# Squama_Ethernet.net
KiCad netlist of a schematic drawn in EAGLE
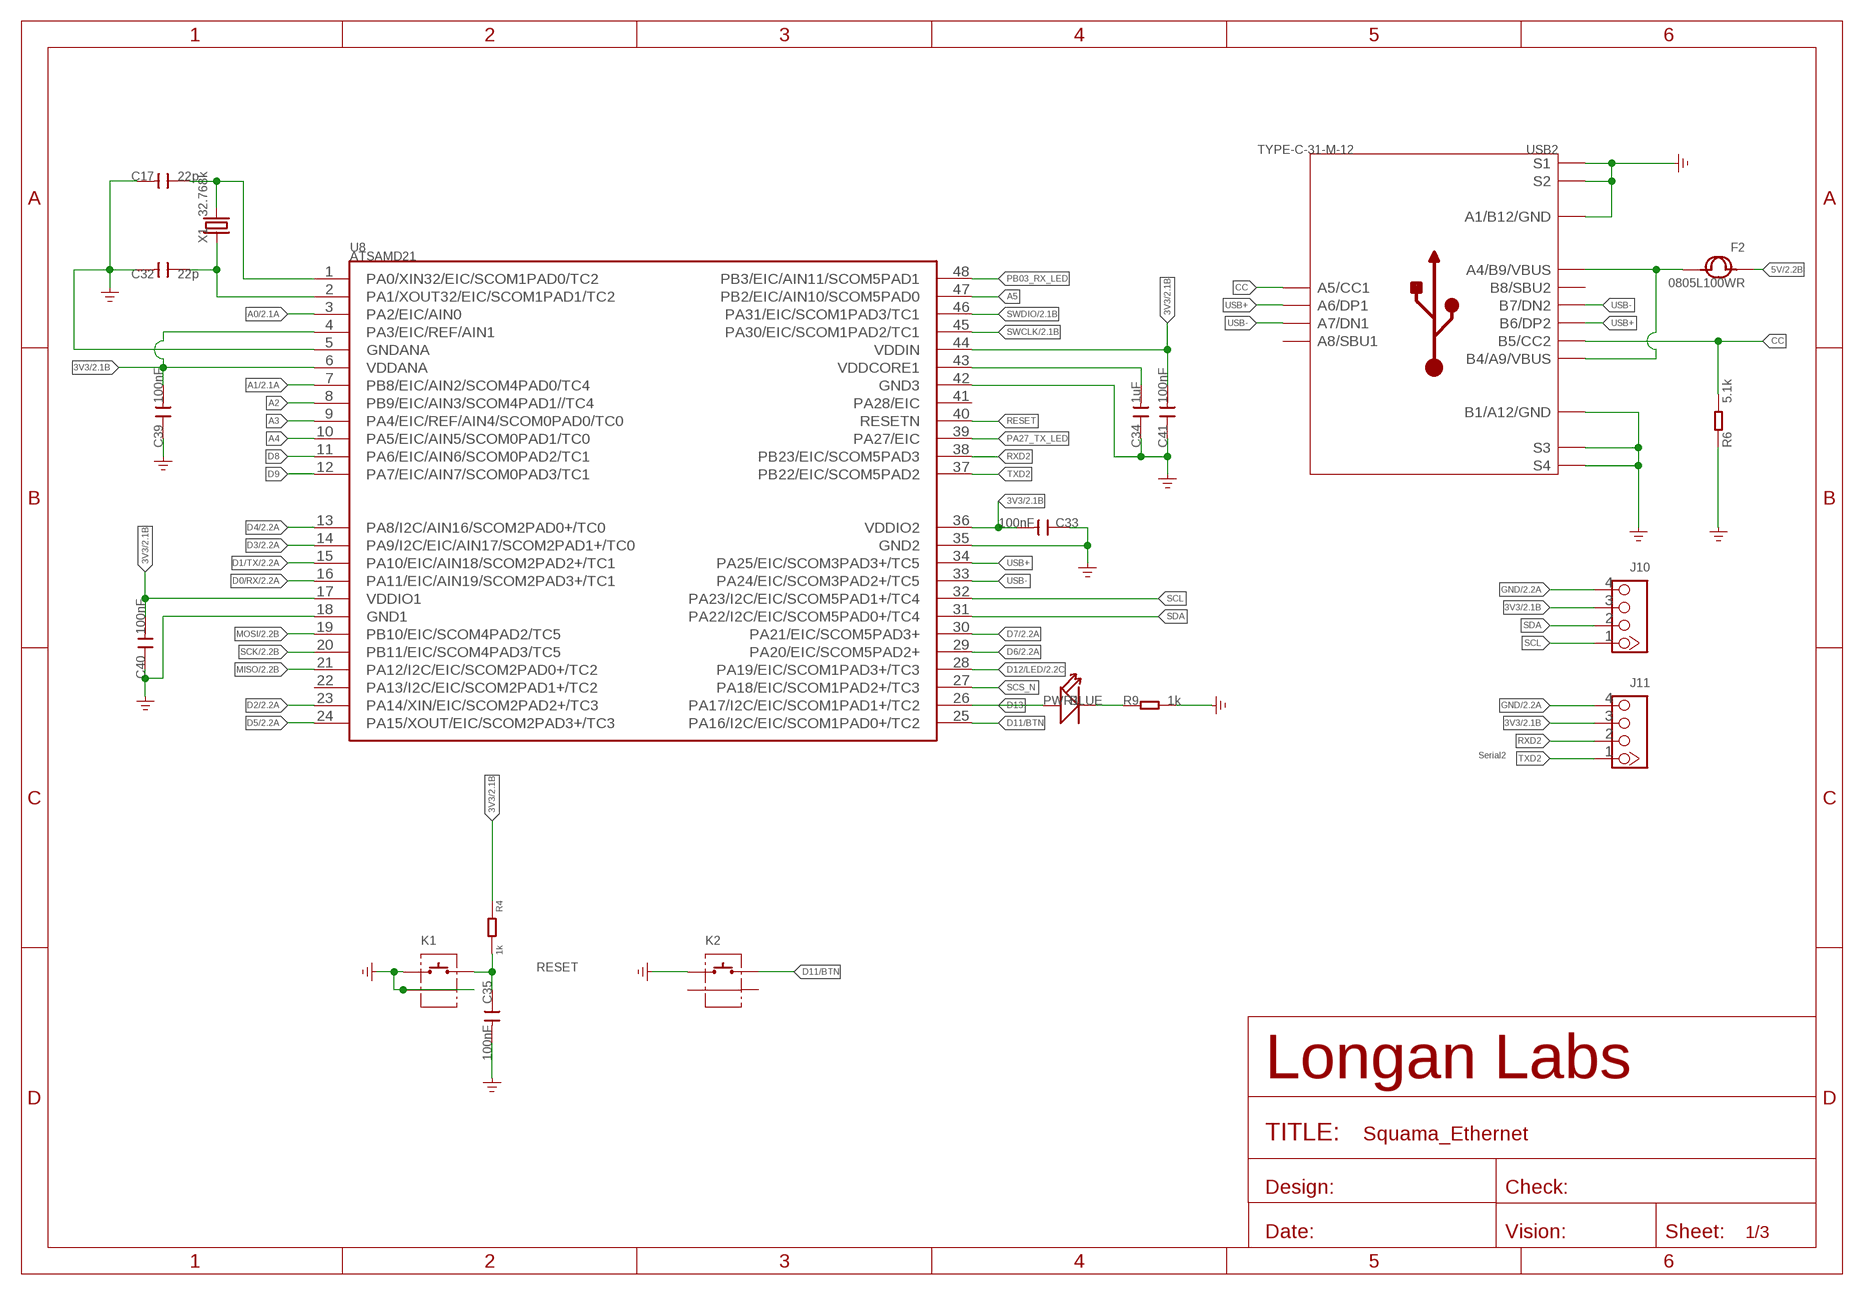
[diagram p0: schematic, sheet 1]
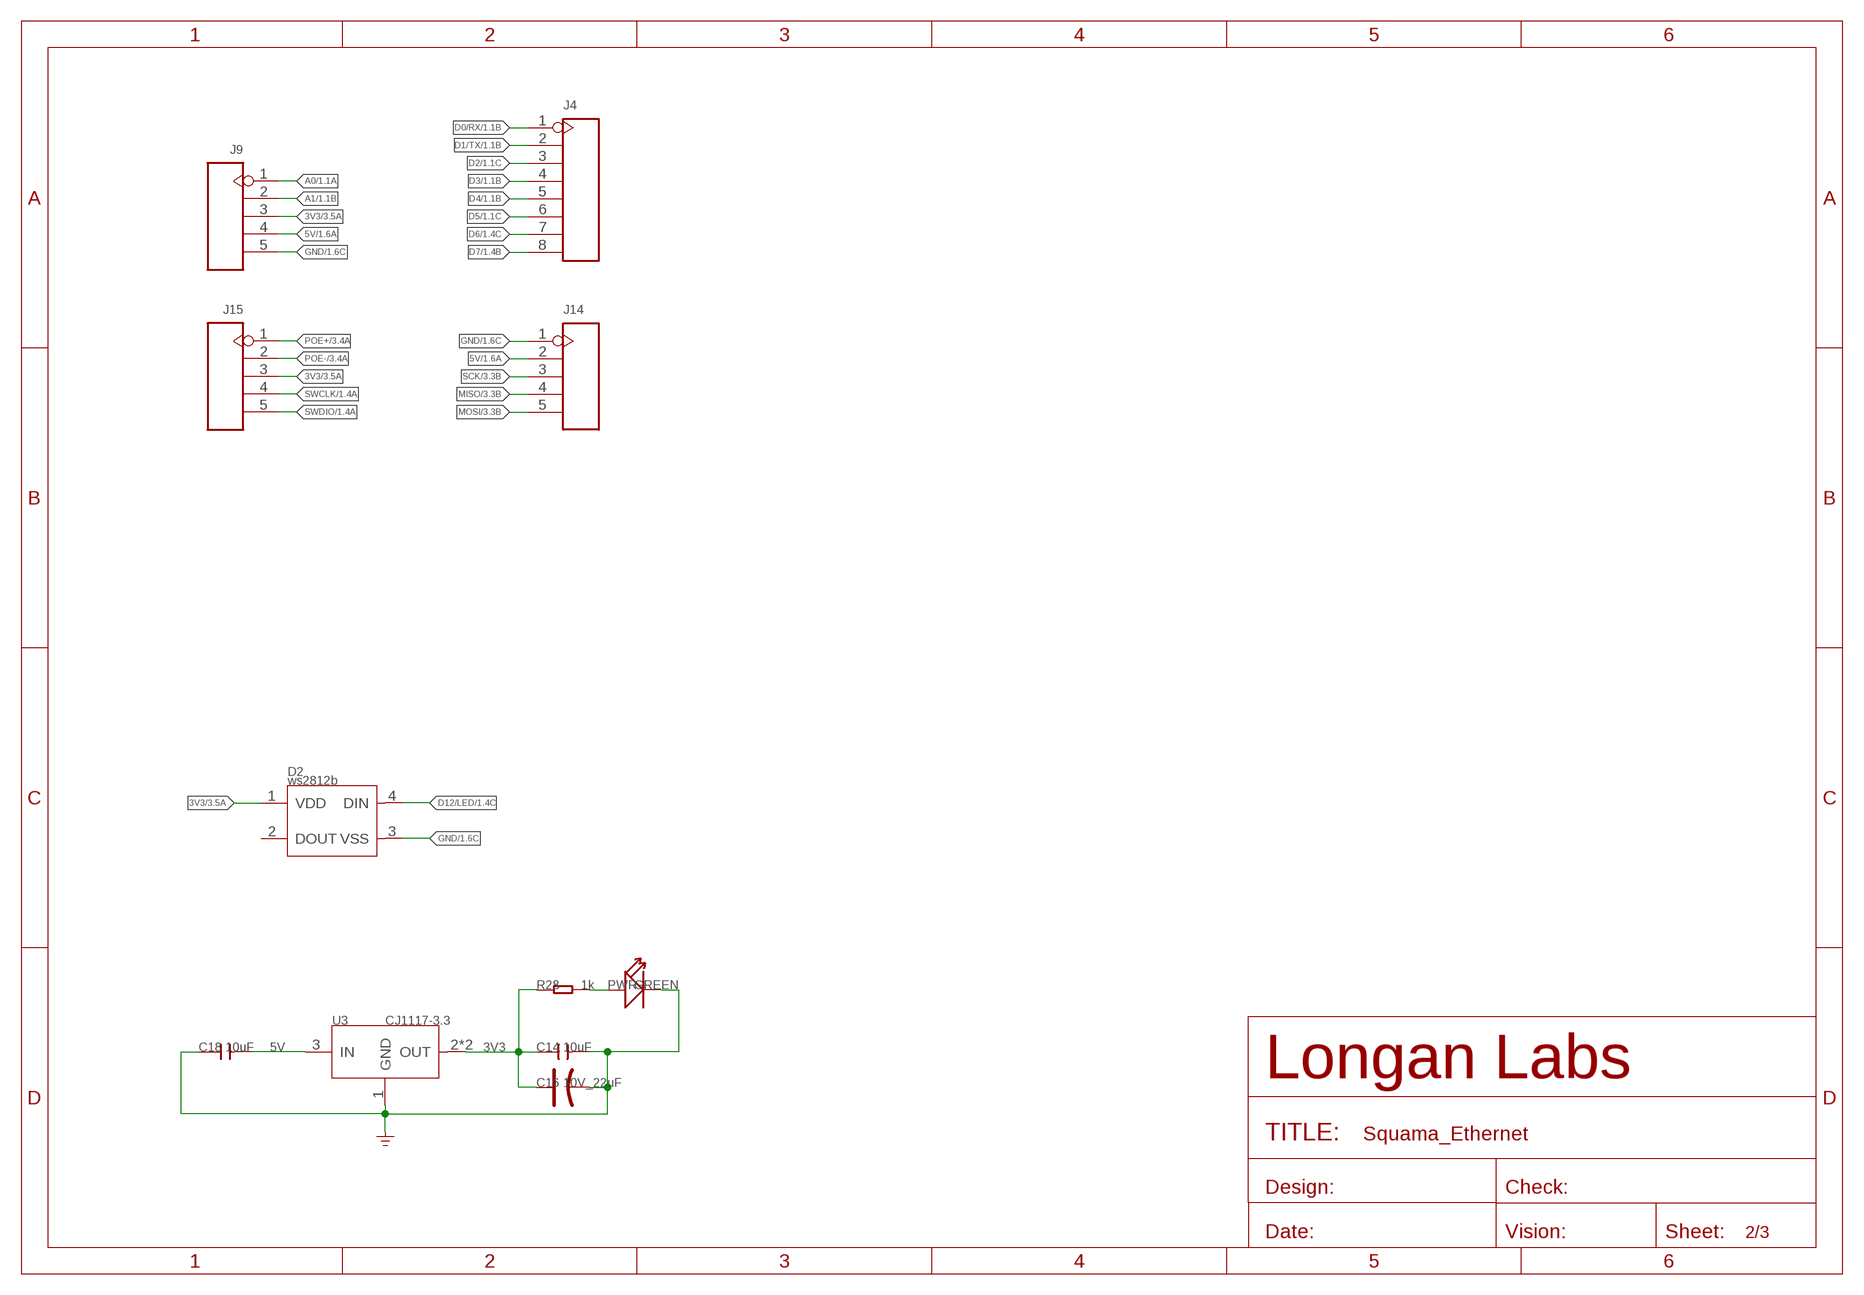
[diagram p1: schematic, sheet 2]
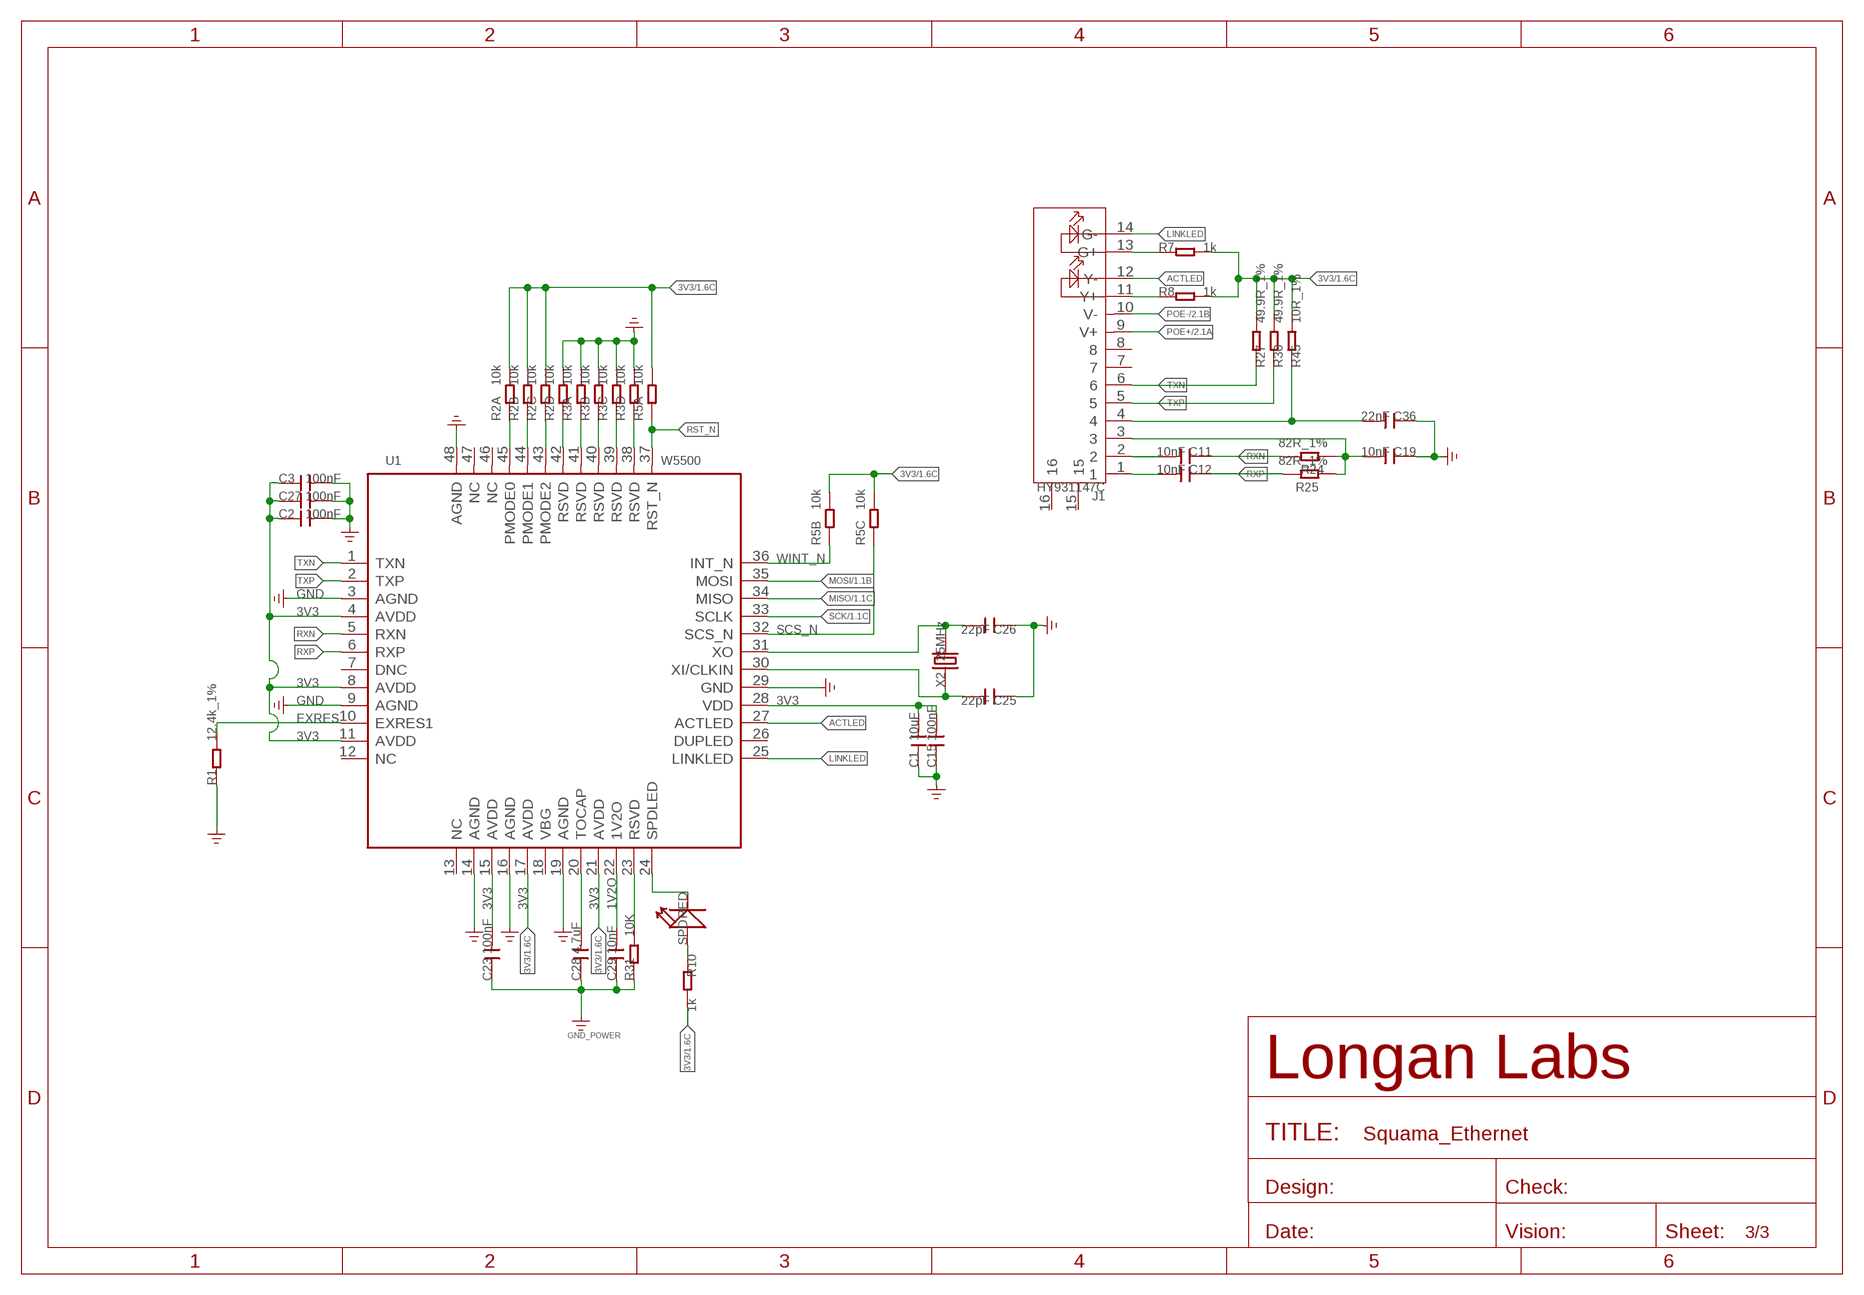
[diagram p2: schematic, sheet 3]

(export (version "E")
  (design (tool "Eeschema 10.0.6"))
  (components
    (comp (ref "C1")
      (value "10uF")
      (footprint "eagle-import:C0603")
      (libsource (lib "eagle-import") (part "C-0603"))
    )
    (comp (ref "C2")
      (value "100nF")
      (footprint "eagle-import:C0603")
      (libsource (lib "eagle-import") (part "C-0603"))
    )
    (comp (ref "C3")
      (value "100nF")
      (footprint "eagle-import:C0603")
      (libsource (lib "eagle-import") (part "C-0603"))
    )
    (comp (ref "C11")
      (value "10nF")
      (footprint "eagle-import:C0603")
      (libsource (lib "eagle-import") (part "C-0603"))
    )
    (comp (ref "C12")
      (value "10nF")
      (footprint "eagle-import:C0603")
      (libsource (lib "eagle-import") (part "C-0603"))
    )
    (comp (ref "C15")
      (value "100nF")
      (footprint "eagle-import:C0603")
      (libsource (lib "eagle-import") (part "C-0603"))
    )
    (comp (ref "C19")
      (value "10nF")
      (footprint "eagle-import:C0603")
      (libsource (lib "eagle-import") (part "C-0603"))
    )
    (comp (ref "C23")
      (value "100nF")
      (footprint "eagle-import:C0603")
      (libsource (lib "eagle-import") (part "C-0603"))
    )
    (comp (ref "C25")
      (value "22pF")
      (footprint "eagle-import:C0603")
      (libsource (lib "eagle-import") (part "C-0603"))
    )
    (comp (ref "C26")
      (value "22pF")
      (footprint "eagle-import:C0603")
      (libsource (lib "eagle-import") (part "C-0603"))
    )
    (comp (ref "C27")
      (value "100nF")
      (footprint "eagle-import:C0603")
      (libsource (lib "eagle-import") (part "C-0603"))
    )
    (comp (ref "C28")
      (value "4.7uF")
      (footprint "eagle-import:C0805")
      (libsource (lib "eagle-import") (part "C-0805"))
    )
    (comp (ref "C29")
      (value "10nF")
      (footprint "eagle-import:C0603")
      (libsource (lib "eagle-import") (part "C-0603"))
    )
    (comp (ref "C36")
      (value "22nF")
      (footprint "eagle-import:C0603")
      (libsource (lib "eagle-import") (part "C-0603"))
    )
    (comp (ref "J1")
      (value "HY931147C")
      (footprint "eagle-import:RJ45-14+2P-16.1X21.6X13.95MM")
      (libsource (lib "eagle-import") (part "RJ45-HY931147C"))
    )
    (comp (ref "R1")
      (value "12.4k_1%")
      (footprint "eagle-import:R0603")
      (libsource (lib "eagle-import") (part "R-0603"))
    )
    (comp (ref "R2")
      (value "10k")
      (footprint "eagle-import:R0804-8")
      (libsource (lib "eagle-import") (part "RES-ARRAY-0804"))
    )
    (comp (ref "R3")
      (value "10k")
      (footprint "eagle-import:R0804-8")
      (libsource (lib "eagle-import") (part "RES-ARRAY-0804"))
    )
    (comp (ref "R5")
      (value "10k")
      (footprint "eagle-import:R0804-8")
      (libsource (lib "eagle-import") (part "RES-ARRAY-0804"))
    )
    (comp (ref "R7")
      (value "1k")
      (footprint "eagle-import:R0603")
      (libsource (lib "eagle-import") (part "R-0603"))
    )
    (comp (ref "R8")
      (value "1k")
      (footprint "eagle-import:R0603")
      (libsource (lib "eagle-import") (part "R-0603"))
    )
    (comp (ref "R10")
      (value "1k")
      (footprint "eagle-import:R0603")
      (libsource (lib "eagle-import") (part "R-0603"))
    )
    (comp (ref "R24")
      (value "82R_1%")
      (footprint "eagle-import:R0603")
      (libsource (lib "eagle-import") (part "R-0603"))
    )
    (comp (ref "R25")
      (value "82R_1%")
      (footprint "eagle-import:R0603")
      (libsource (lib "eagle-import") (part "R-0603"))
    )
    (comp (ref "R27")
      (value "49.9R_1%")
      (footprint "eagle-import:R0603")
      (libsource (lib "eagle-import") (part "R-0603"))
    )
    (comp (ref "R30")
      (value "49.9R_1%")
      (footprint "eagle-import:R0603")
      (libsource (lib "eagle-import") (part "R-0603"))
    )
    (comp (ref "R31")
      (value "10K")
      (footprint "eagle-import:R0603")
      (libsource (lib "eagle-import") (part "R-0603"))
    )
    (comp (ref "R45")
      (value "10R_1%")
      (footprint "eagle-import:R0603")
      (libsource (lib "eagle-import") (part "R-0603"))
    )
    (comp (ref "SPD")
      (value "RED")
      (footprint "eagle-import:LED-0603")
      (libsource (lib "eagle-import") (part "LED'0603'"))
    )
    (comp (ref "U1")
      (value "W5500")
      (footprint "eagle-import:LQFP-48")
      (libsource (lib "eagle-import") (part "DRIVER-W5500"))
    )
    (comp (ref "X2")
      (value "25MHz")
      (footprint "eagle-import:2P-SMD-5X3.2")
      (libsource (lib "eagle-import") (part "CRYSTAL'5032'"))
    )
    (comp (ref "C14")
      (value "10uF")
      (footprint "eagle-import:C0805")
      (libsource (lib "eagle-import") (part "C-0805"))
    )
    (comp (ref "C16")
      (value "10V_22uF")
      (footprint "eagle-import:AVX-B")
      (libsource (lib "eagle-import") (part "CAP-AVX-B"))
    )
    (comp (ref "C18")
      (value "10uF")
      (footprint "eagle-import:C0805")
      (libsource (lib "eagle-import") (part "C-0805"))
    )
    (comp (ref "D2")
      (value "ws2812b")
      (footprint "eagle-import:LED4-SMD-5050")
      (libsource (lib "eagle-import") (part "LED-RGB-4P-WS2812B-304990003"))
    )
    (comp (ref "J4")
      (value "HEADER-8P-80/40MIL")
      (footprint "eagle-import:H8-2.54-C80D40MIL")
      (libsource (lib "eagle-import") (part "HEADER-8P-80/40MIL"))
    )
    (comp (ref "J9")
      (value "HEADER-5P-2.54")
      (footprint "eagle-import:H5-2.54")
      (libsource (lib "eagle-import") (part "HEADER-5P-2.54"))
    )
    (comp (ref "J14")
      (value "HEADER-5P-2.0")
      (footprint "eagle-import:H5-2.0")
      (libsource (lib "eagle-import") (part "HEADER-5P-2.0"))
    )
    (comp (ref "J15")
      (value "HEADER-5P-2.0")
      (footprint "eagle-import:H5-2.0")
      (libsource (lib "eagle-import") (part "HEADER-5P-2.0"))
    )
    (comp (ref "PWR")
      (value "GREEN")
      (footprint "eagle-import:LED-0603")
      (libsource (lib "eagle-import") (part "LED'0603'"))
    )
    (comp (ref "R28")
      (value "1k")
      (footprint "eagle-import:R0603")
      (libsource (lib "eagle-import") (part "R-0603"))
    )
    (comp (ref "U3")
      (value "CJ1117-3.3")
      (footprint "eagle-import:SOT-89")
      (libsource (lib "eagle-import") (part "PMIC-CJ1117'SOT89'"))
    )
    (comp (ref "C17")
      (value "22p")
      (footprint "eagle-import:C0603")
      (libsource (lib "eagle-import") (part "CAP-0603"))
    )
    (comp (ref "C32")
      (value "22p")
      (footprint "eagle-import:C0603")
      (libsource (lib "eagle-import") (part "CAP-0603"))
    )
    (comp (ref "C33")
      (value "100nF")
      (footprint "eagle-import:C0603")
      (libsource (lib "eagle-import") (part "CAP-0603"))
    )
    (comp (ref "C34")
      (value "1uF")
      (footprint "eagle-import:C0603")
      (libsource (lib "eagle-import") (part "CAP-0603"))
    )
    (comp (ref "C35")
      (value "100nF")
      (footprint "eagle-import:C0603")
      (libsource (lib "eagle-import") (part "CAP-0603"))
    )
    (comp (ref "C39")
      (value "100nF")
      (footprint "eagle-import:C0603")
      (libsource (lib "eagle-import") (part "CAP-0603"))
    )
    (comp (ref "C40")
      (value "100nF")
      (footprint "eagle-import:C0603")
      (libsource (lib "eagle-import") (part "CAP-0603"))
    )
    (comp (ref "C41")
      (value "100nF")
      (footprint "eagle-import:C0603")
      (libsource (lib "eagle-import") (part "CAP-0603"))
    )
    (comp (ref "F2")
      (value "0805L100WR")
      (footprint "eagle-import:F0805")
      (libsource (lib "eagle-import") (part "FUSE0805"))
    )
    (comp (ref "J10")
      (value "320110033")
      (footprint "eagle-import:HW4-2.0")
      (libsource (lib "eagle-import") (part "GROVE-CONNECTOR-DIP-2.0"))
    )
    (comp (ref "J11")
      (value "320110033")
      (footprint "eagle-import:HW4-2.0")
      (libsource (lib "eagle-import") (part "GROVE-CONNECTOR-DIP-2.0"))
    )
    (comp (ref "K1")
      (value "BUTTON-2+2P")
      (footprint "eagle-import:SW2+2P-7.7X2.75X3.95MM")
      (libsource (lib "eagle-import") (part "BUTTON-2+2P"))
    )
    (comp (ref "K2")
      (value "BUTTON-2+2P")
      (footprint "eagle-import:SW2+2P-7.7X2.75X3.95MM")
      (libsource (lib "eagle-import") (part "BUTTON-2+2P"))
    )
    (comp (ref "PWR1")
      (value "BLUE")
      (footprint "eagle-import:LED-0603")
      (libsource (lib "eagle-import") (part "LED'0603'"))
    )
    (comp (ref "R4")
      (value "1k")
      (footprint "eagle-import:R0603")
      (libsource (lib "eagle-import") (part "RES-0603"))
    )
    (comp (ref "R6")
      (value "5.1k")
      (footprint "eagle-import:R0603")
      (libsource (lib "eagle-import") (part "RES-0603"))
    )
    (comp (ref "R9")
      (value "1k")
      (footprint "eagle-import:R0603")
      (libsource (lib "eagle-import") (part "R-0603"))
    )
    (comp (ref "U8")
      (value "ATSAMD21")
      (footprint "eagle-import:TQFP48-0.5-7X7MM")
      (libsource (lib "eagle-import") (part "MCU-ATSAMD21-TQFP48"))
    )
    (comp (ref "USB2")
      (value "TYPE-C-31-M-12")
      (footprint "eagle-import:USB2.0-TYPE-C")
      (libsource (lib "eagle-import") (part "USB2.0-TYPE-C"))
    )
    (comp (ref "X1")
      (value "32.768k")
      (footprint "eagle-import:X2-SMD-3.2X1.5X0.55MM")
      (libsource (lib "eagle-import") (part "CRYSTAL-2P-3215"))
    )
  )
  (nets
    (net (code "1") (name "1V2O") (class "Default")
      (node (ref "C29") (pin "2") (pinfunction "2_2") (pintype "passive"))
      (node (ref "U1") (pin "22") (pinfunction "1V2O_22") (pintype "passive"))
    )
    (net (code "2") (name "3V3") (class "Default")
      (node (ref "C1") (pin "2") (pinfunction "2_2") (pintype "passive"))
      (node (ref "C14") (pin "1") (pinfunction "1_1") (pintype "passive"))
      (node (ref "C15") (pin "2") (pinfunction "2_2") (pintype "passive"))
      (node (ref "C16") (pin "+") (pinfunction "+_+") (pintype "passive"))
      (node (ref "C2") (pin "1") (pinfunction "1_1") (pintype "passive"))
      (node (ref "C23") (pin "2") (pinfunction "2_2") (pintype "passive"))
      (node (ref "C27") (pin "1") (pinfunction "1_1") (pintype "passive"))
      (node (ref "C3") (pin "1") (pinfunction "1_1") (pintype "passive"))
      (node (ref "C33") (pin "2") (pinfunction "2_2") (pintype "passive"))
      (node (ref "C39") (pin "2") (pinfunction "2_2") (pintype "passive"))
      (node (ref "C40") (pin "2") (pinfunction "2_2") (pintype "passive"))
      (node (ref "C41") (pin "2") (pinfunction "2_2") (pintype "passive"))
      (node (ref "D2") (pin "1") (pinfunction "VDD_1") (pintype "bidirectional"))
      (node (ref "J10") (pin "3") (pinfunction "3_3") (pintype "bidirectional"))
      (node (ref "J11") (pin "3") (pinfunction "3_3") (pintype "bidirectional"))
      (node (ref "J15") (pin "3") (pinfunction "3_3") (pintype "bidirectional"))
      (node (ref "J9") (pin "3") (pinfunction "3_3") (pintype "bidirectional"))
      (node (ref "R10") (pin "2") (pinfunction "2_2") (pintype "passive"))
      (node (ref "R2") (pin "6") (pinfunction "2_6") (pintype "passive"))
      (node (ref "R2") (pin "7") (pinfunction "2_7") (pintype "passive"))
      (node (ref "R2") (pin "8") (pinfunction "2_8") (pintype "passive"))
      (node (ref "R27") (pin "2") (pinfunction "2_2") (pintype "passive"))
      (node (ref "R28") (pin "1") (pinfunction "1_1") (pintype "passive"))
      (node (ref "R30") (pin "2") (pinfunction "2_2") (pintype "passive"))
      (node (ref "R4") (pin "1") (pinfunction "1_1") (pintype "passive"))
      (node (ref "R45") (pin "2") (pinfunction "2_2") (pintype "passive"))
      (node (ref "R5") (pin "6") (pinfunction "2_6") (pintype "passive"))
      (node (ref "R5") (pin "7") (pinfunction "2_7") (pintype "passive"))
      (node (ref "R5") (pin "8") (pinfunction "2_8") (pintype "passive"))
      (node (ref "R7") (pin "2") (pinfunction "2_2") (pintype "passive"))
      (node (ref "R8") (pin "2") (pinfunction "2_2") (pintype "passive"))
      (node (ref "U1") (pin "11") (pinfunction "AVDD_11") (pintype "passive"))
      (node (ref "U1") (pin "15") (pinfunction "AVDD_15") (pintype "passive"))
      (node (ref "U1") (pin "17") (pinfunction "AVDD_17") (pintype "passive"))
      (node (ref "U1") (pin "21") (pinfunction "AVDD_21") (pintype "passive"))
      (node (ref "U1") (pin "28") (pinfunction "VDD_28") (pintype "passive"))
      (node (ref "U1") (pin "4") (pinfunction "AVDD_4") (pintype "passive"))
      (node (ref "U1") (pin "8") (pinfunction "AVDD_8") (pintype "passive"))
      (node (ref "U3") (pin "2") (pinfunction "OUT_2") (pintype "bidirectional"))
      (node (ref "U3") (pin "4") (pinfunction "OUT_4") (pintype "bidirectional"))
      (node (ref "U8") (pin "17") (pinfunction "VDDIO1_17") (pintype "power_in"))
      (node (ref "U8") (pin "36") (pinfunction "VDDIO2_36") (pintype "power_in"))
      (node (ref "U8") (pin "4") (pinfunction "PA3/EIC/REF/AIN1_4") (pintype "bidirectional"))
      (node (ref "U8") (pin "44") (pinfunction "VDDIN_44") (pintype "power_in"))
      (node (ref "U8") (pin "6") (pinfunction "VDDANA_6") (pintype "power_in"))
    )
    (net (code "3") (name "5V") (class "Default")
      (node (ref "C18") (pin "2") (pinfunction "2_2") (pintype "passive"))
      (node (ref "F2") (pin "1") (pinfunction "1_1") (pintype "bidirectional"))
      (node (ref "J14") (pin "2") (pinfunction "2_2") (pintype "bidirectional"))
      (node (ref "J9") (pin "4") (pinfunction "4_4") (pintype "bidirectional"))
      (node (ref "U3") (pin "3") (pinfunction "IN_3") (pintype "bidirectional"))
    )
    (net (code "4") (name "A0") (class "Default")
      (node (ref "J9") (pin "1") (pinfunction "1_1") (pintype "bidirectional"))
      (node (ref "U8") (pin "3") (pinfunction "PA2/EIC/AIN0_3") (pintype "bidirectional"))
    )
    (net (code "5") (name "A1") (class "Default")
      (node (ref "J9") (pin "2") (pinfunction "2_2") (pintype "bidirectional"))
      (node (ref "U8") (pin "7") (pinfunction "PB8/EIC/AIN2/SCOM4PAD0/TC4_7") (pintype "bidirectional"))
    )
    (net (code "6") (name "A2") (class "Default")
      (node (ref "U8") (pin "8") (pinfunction "PB9/EIC/AIN3/SCOM4PAD1//TC4_8") (pintype "bidirectional"))
    )
    (net (code "7") (name "A3") (class "Default")
      (node (ref "U8") (pin "9") (pinfunction "PA4/EIC/REF/AIN4/SCOM0PAD0/TC0_9") (pintype "bidirectional"))
    )
    (net (code "8") (name "A4") (class "Default")
      (node (ref "U8") (pin "10") (pinfunction "PA5/EIC/AIN5/SCOM0PAD1/TC0_10") (pintype "bidirectional"))
    )
    (net (code "9") (name "A5") (class "Default")
      (node (ref "U8") (pin "47") (pinfunction "PB2/EIC/AIN10/SCOM5PAD0_47") (pintype "bidirectional"))
    )
    (net (code "10") (name "ACTLED") (class "Default")
      (node (ref "J1") (pin "12") (pinfunction "Y-_12") (pintype "bidirectional"))
      (node (ref "U1") (pin "27") (pinfunction "ACTLED_27") (pintype "passive"))
    )
    (net (code "11") (name "CC") (class "Default")
      (node (ref "R6") (pin "2") (pinfunction "2_2") (pintype "passive"))
      (node (ref "USB2") (pin "A5") (pinfunction "A5/CC1_A5") (pintype "bidirectional"))
      (node (ref "USB2") (pin "B5") (pinfunction "B5/CC2_B5") (pintype "bidirectional"))
    )
    (net (code "12") (name "D0{slash}RX") (class "Default")
      (node (ref "J4") (pin "1") (pinfunction "1_1") (pintype "bidirectional"))
      (node (ref "U8") (pin "16") (pinfunction "PA11/EIC/AIN19/SCOM2PAD3+/TC1_16") (pintype "bidirectional"))
    )
    (net (code "13") (name "D1{slash}TX") (class "Default")
      (node (ref "J4") (pin "2") (pinfunction "2_2") (pintype "bidirectional"))
      (node (ref "U8") (pin "15") (pinfunction "PA10/EIC/AIN18/SCOM2PAD2+/TC1_15") (pintype "bidirectional"))
    )
    (net (code "14") (name "D2") (class "Default")
      (node (ref "J4") (pin "3") (pinfunction "3_3") (pintype "bidirectional"))
      (node (ref "U8") (pin "23") (pinfunction "PA14/XIN/EIC/SCOM2PAD2+/TC3_23") (pintype "bidirectional"))
    )
    (net (code "15") (name "D3") (class "Default")
      (node (ref "J4") (pin "4") (pinfunction "4_4") (pintype "bidirectional"))
      (node (ref "U8") (pin "14") (pinfunction "PA9/I2C/EIC/AIN17/SCOM2PAD1+/TC0_14") (pintype "bidirectional"))
    )
    (net (code "16") (name "D4") (class "Default")
      (node (ref "J4") (pin "5") (pinfunction "5_5") (pintype "bidirectional"))
      (node (ref "U8") (pin "13") (pinfunction "PA8/I2C/AIN16/SCOM2PAD0+/TC0_13") (pintype "bidirectional"))
    )
    (net (code "17") (name "D5") (class "Default")
      (node (ref "J4") (pin "6") (pinfunction "6_6") (pintype "bidirectional"))
      (node (ref "U8") (pin "24") (pinfunction "PA15/XOUT/EIC/SCOM2PAD3+/TC3_24") (pintype "bidirectional"))
    )
    (net (code "18") (name "D6") (class "Default")
      (node (ref "J4") (pin "7") (pinfunction "7_7") (pintype "bidirectional"))
      (node (ref "U8") (pin "29") (pinfunction "PA20/EIC/SCOM5PAD2+_29") (pintype "bidirectional"))
    )
    (net (code "19") (name "D7") (class "Default")
      (node (ref "J4") (pin "8") (pinfunction "8_8") (pintype "bidirectional"))
      (node (ref "U8") (pin "30") (pinfunction "PA21/EIC/SCOM5PAD3+_30") (pintype "bidirectional"))
    )
    (net (code "20") (name "D8") (class "Default")
      (node (ref "U8") (pin "11") (pinfunction "PA6/EIC/AIN6/SCOM0PAD2/TC1_11") (pintype "bidirectional"))
    )
    (net (code "21") (name "D9") (class "Default")
      (node (ref "U8") (pin "12") (pinfunction "PA7/EIC/AIN7/SCOM0PAD3/TC1_12") (pintype "bidirectional"))
    )
    (net (code "22") (name "D11{slash}BTN") (class "Default")
      (node (ref "K2") (pin "2") (pinfunction "2_2") (pintype "bidirectional"))
      (node (ref "U8") (pin "25") (pinfunction "PA16/I2C/EIC/SCOM1PAD0+/TC2_25") (pintype "bidirectional"))
    )
    (net (code "23") (name "D12{slash}LED") (class "Default")
      (node (ref "D2") (pin "4") (pinfunction "DIN_4") (pintype "bidirectional"))
      (node (ref "U8") (pin "28") (pinfunction "PA19/EIC/SCOM1PAD3+/TC3_28") (pintype "bidirectional"))
    )
    (net (code "24") (name "D13") (class "Default")
      (node (ref "PWR1") (pin "+") (pinfunction "+_+") (pintype "passive"))
      (node (ref "U8") (pin "26") (pinfunction "PA17/I2C/EIC/SCOM1PAD1+/TC2_26") (pintype "bidirectional"))
    )
    (net (code "25") (name "EXRES") (class "Default")
      (node (ref "R1") (pin "2") (pinfunction "2_2") (pintype "passive"))
      (node (ref "U1") (pin "10") (pinfunction "EXRES1_10") (pintype "passive"))
    )
    (net (code "26") (name "GND") (class "Default")
      (node (ref "C1") (pin "1") (pinfunction "1_1") (pintype "passive"))
      (node (ref "C14") (pin "2") (pinfunction "2_2") (pintype "passive"))
      (node (ref "C15") (pin "1") (pinfunction "1_1") (pintype "passive"))
      (node (ref "C16") (pin "-") (pinfunction "-_-") (pintype "passive"))
      (node (ref "C17") (pin "2") (pinfunction "2_2") (pintype "passive"))
      (node (ref "C18") (pin "1") (pinfunction "1_1") (pintype "passive"))
      (node (ref "C19") (pin "1") (pinfunction "1_1") (pintype "passive"))
      (node (ref "C2") (pin "2") (pinfunction "2_2") (pintype "passive"))
      (node (ref "C23") (pin "1") (pinfunction "1_1") (pintype "passive"))
      (node (ref "C25") (pin "1") (pinfunction "1_1") (pintype "passive"))
      (node (ref "C26") (pin "1") (pinfunction "1_1") (pintype "passive"))
      (node (ref "C27") (pin "2") (pinfunction "2_2") (pintype "passive"))
      (node (ref "C28") (pin "1") (pinfunction "1_1") (pintype "passive"))
      (node (ref "C29") (pin "1") (pinfunction "1_1") (pintype "passive"))
      (node (ref "C3") (pin "2") (pinfunction "2_2") (pintype "passive"))
      (node (ref "C32") (pin "2") (pinfunction "2_2") (pintype "passive"))
      (node (ref "C33") (pin "1") (pinfunction "1_1") (pintype "passive"))
      (node (ref "C34") (pin "1") (pinfunction "1_1") (pintype "passive"))
      (node (ref "C35") (pin "2") (pinfunction "2_2") (pintype "passive"))
      (node (ref "C36") (pin "1") (pinfunction "1_1") (pintype "passive"))
      (node (ref "C39") (pin "1") (pinfunction "1_1") (pintype "passive"))
      (node (ref "C40") (pin "1") (pinfunction "1_1") (pintype "passive"))
      (node (ref "C41") (pin "1") (pinfunction "1_1") (pintype "passive"))
      (node (ref "D2") (pin "3") (pinfunction "VSS_3") (pintype "bidirectional"))
      (node (ref "J10") (pin "4") (pinfunction "4_4") (pintype "bidirectional"))
      (node (ref "J11") (pin "4") (pinfunction "4_4") (pintype "bidirectional"))
      (node (ref "J14") (pin "1") (pinfunction "1_1") (pintype "bidirectional"))
      (node (ref "J9") (pin "5") (pinfunction "5_5") (pintype "bidirectional"))
      (node (ref "K1") (pin "1") (pinfunction "1_1") (pintype "bidirectional"))
      (node (ref "K1") (pin "S1") (pinfunction "S1_S1") (pintype "bidirectional"))
      (node (ref "K1") (pin "S2") (pinfunction "S2_S2") (pintype "bidirectional"))
      (node (ref "K2") (pin "1") (pinfunction "1_1") (pintype "bidirectional"))
      (node (ref "PWR") (pin "-") (pinfunction "-_-") (pintype "passive"))
      (node (ref "R1") (pin "1") (pinfunction "1_1") (pintype "passive"))
      (node (ref "R2") (pin "5") (pinfunction "2_5") (pintype "passive"))
      (node (ref "R3") (pin "5") (pinfunction "2_5") (pintype "passive"))
      (node (ref "R3") (pin "6") (pinfunction "2_6") (pintype "passive"))
      (node (ref "R3") (pin "7") (pinfunction "2_7") (pintype "passive"))
      (node (ref "R3") (pin "8") (pinfunction "2_8") (pintype "passive"))
      (node (ref "R31") (pin "1") (pinfunction "1_1") (pintype "passive"))
      (node (ref "R6") (pin "1") (pinfunction "1_1") (pintype "passive"))
      (node (ref "R9") (pin "2") (pinfunction "2_2") (pintype "passive"))
      (node (ref "U1") (pin "14") (pinfunction "AGND_14") (pintype "passive"))
      (node (ref "U1") (pin "16") (pinfunction "AGND_16") (pintype "passive"))
      (node (ref "U1") (pin "19") (pinfunction "AGND_19") (pintype "passive"))
      (node (ref "U1") (pin "29") (pinfunction "GND_29") (pintype "passive"))
      (node (ref "U1") (pin "3") (pinfunction "AGND_3") (pintype "passive"))
      (node (ref "U1") (pin "48") (pinfunction "AGND_48") (pintype "passive"))
      (node (ref "U1") (pin "9") (pinfunction "AGND_9") (pintype "passive"))
      (node (ref "U3") (pin "1") (pinfunction "GND_1") (pintype "bidirectional"))
      (node (ref "U8") (pin "18") (pinfunction "GND1_18") (pintype "power_in"))
      (node (ref "U8") (pin "35") (pinfunction "GND2_35") (pintype "power_in"))
      (node (ref "U8") (pin "42") (pinfunction "GND3_42") (pintype "power_in"))
      (node (ref "U8") (pin "5") (pinfunction "GNDANA_5") (pintype "power_in"))
      (node (ref "USB2") (pin "A1_B12") (pinfunction "A1/B12/GND_A1_B12") (pintype "bidirectional"))
      (node (ref "USB2") (pin "B1_A12") (pinfunction "B1/A12/GND_B1_A12") (pintype "bidirectional"))
      (node (ref "USB2") (pin "S1") (pinfunction "S1_S1") (pintype "bidirectional"))
      (node (ref "USB2") (pin "S2") (pinfunction "S2_S2") (pintype "bidirectional"))
      (node (ref "USB2") (pin "S3") (pinfunction "S3_S3") (pintype "bidirectional"))
      (node (ref "USB2") (pin "S4") (pinfunction "S4_S4") (pintype "bidirectional"))
      (node (ref "USB2") (pin "S5") (pinfunction "S1_S5") (pintype "bidirectional"))
      (node (ref "USB2") (pin "S6") (pinfunction "S2_S6") (pintype "bidirectional"))
    )
    (net (code "27") (name "LINKLED") (class "Default")
      (node (ref "J1") (pin "14") (pinfunction "G-_14") (pintype "bidirectional"))
      (node (ref "U1") (pin "25") (pinfunction "LINKLED_25") (pintype "passive"))
    )
    (net (code "28") (name "MISO") (class "Default")
      (node (ref "J14") (pin "4") (pinfunction "4_4") (pintype "bidirectional"))
      (node (ref "U1") (pin "34") (pinfunction "MISO_34") (pintype "passive"))
      (node (ref "U8") (pin "21") (pinfunction "PA12/I2C/EIC/SCOM2PAD0+/TC2_21") (pintype "bidirectional"))
    )
    (net (code "29") (name "MOSI") (class "Default")
      (node (ref "J14") (pin "5") (pinfunction "5_5") (pintype "bidirectional"))
      (node (ref "U1") (pin "35") (pinfunction "MOSI_35") (pintype "passive"))
      (node (ref "U8") (pin "19") (pinfunction "PB10/EIC/SCOM4PAD2/TC5_19") (pintype "bidirectional"))
    )
    (net (code "30") (name "Net-(C11-Pad2)") (class "Default")
      (node (ref "C11") (pin "2") (pinfunction "2_2") (pintype "passive"))
      (node (ref "J1") (pin "2") (pinfunction "2_2") (pintype "bidirectional"))
    )
    (net (code "31") (name "Net-(C12-Pad2)") (class "Default")
      (node (ref "C12") (pin "2") (pinfunction "2_2") (pintype "passive"))
      (node (ref "J1") (pin "1") (pinfunction "1_1") (pintype "bidirectional"))
    )
    (net (code "32") (name "Net-(C19-Pad2)") (class "Default")
      (node (ref "C19") (pin "2") (pinfunction "2_2") (pintype "passive"))
      (node (ref "J1") (pin "3") (pinfunction "3_3") (pintype "bidirectional"))
      (node (ref "R24") (pin "2") (pinfunction "2_2") (pintype "passive"))
      (node (ref "R25") (pin "1") (pinfunction "1_1") (pintype "passive"))
    )
    (net (code "33") (name "Net-(C36-Pad2)") (class "Default")
      (node (ref "C36") (pin "2") (pinfunction "2_2") (pintype "passive"))
      (node (ref "J1") (pin "4") (pinfunction "4_4") (pintype "bidirectional"))
      (node (ref "R45") (pin "1") (pinfunction "1_1") (pintype "passive"))
    )
    (net (code "34") (name "Net-(J1-G+)") (class "Default")
      (node (ref "J1") (pin "13") (pinfunction "G+_13") (pintype "bidirectional"))
      (node (ref "R7") (pin "1") (pinfunction "1_1") (pintype "passive"))
    )
    (net (code "35") (name "Net-(J1-Y+)") (class "Default")
      (node (ref "J1") (pin "11") (pinfunction "Y+_11") (pintype "bidirectional"))
      (node (ref "R8") (pin "1") (pinfunction "1_1") (pintype "passive"))
    )
    (net (code "36") (name "Net-(PWR-Pad+)") (class "Default")
      (node (ref "PWR") (pin "+") (pinfunction "+_+") (pintype "passive"))
      (node (ref "R28") (pin "2") (pinfunction "2_2") (pintype "passive"))
    )
    (net (code "37") (name "Net-(PWR1-Pad-)") (class "Default")
      (node (ref "PWR1") (pin "-") (pinfunction "-_-") (pintype "passive"))
      (node (ref "R9") (pin "1") (pinfunction "1_1") (pintype "passive"))
    )
    (net (code "38") (name "Net-(R2B-1)") (class "Default")
      (node (ref "R2") (pin "2") (pinfunction "1_2") (pintype "passive"))
      (node (ref "U1") (pin "44") (pinfunction "PMODE1_44") (pintype "passive"))
    )
    (net (code "39") (name "Net-(R2C-1)") (class "Default")
      (node (ref "R2") (pin "3") (pinfunction "1_3") (pintype "passive"))
      (node (ref "U1") (pin "43") (pinfunction "PMODE2_43") (pintype "passive"))
    )
    (net (code "40") (name "Net-(R2D-1)") (class "Default")
      (node (ref "R2") (pin "4") (pinfunction "1_4") (pintype "passive"))
      (node (ref "U1") (pin "42") (pinfunction "RSVD_42") (pintype "passive"))
    )
    (net (code "41") (name "Net-(R3-Pad1)") (class "Default")
      (node (ref "R3") (pin "1") (pinfunction "1_1") (pintype "passive"))
      (node (ref "U1") (pin "41") (pinfunction "RSVD_41") (pintype "passive"))
    )
    (net (code "42") (name "Net-(R3B-1)") (class "Default")
      (node (ref "R3") (pin "2") (pinfunction "1_2") (pintype "passive"))
      (node (ref "U1") (pin "40") (pinfunction "RSVD_40") (pintype "passive"))
    )
    (net (code "43") (name "Net-(R3C-1)") (class "Default")
      (node (ref "R3") (pin "3") (pinfunction "1_3") (pintype "passive"))
      (node (ref "U1") (pin "39") (pinfunction "RSVD_39") (pintype "passive"))
    )
    (net (code "44") (name "Net-(R3D-1)") (class "Default")
      (node (ref "R3") (pin "4") (pinfunction "1_4") (pintype "passive"))
      (node (ref "U1") (pin "38") (pinfunction "RSVD_38") (pintype "passive"))
    )
    (net (code "45") (name "Net-(R10-Pad1)") (class "Default")
      (node (ref "R10") (pin "1") (pinfunction "1_1") (pintype "passive"))
      (node (ref "SPD") (pin "+") (pinfunction "+_+") (pintype "passive"))
    )
    (net (code "46") (name "Net-(R31-Pad2)") (class "Default")
      (node (ref "R31") (pin "2") (pinfunction "2_2") (pintype "passive"))
      (node (ref "U1") (pin "23") (pinfunction "RSVD_23") (pintype "passive"))
    )
    (net (code "47") (name "Net-(U1-PMODE0)") (class "Default")
      (node (ref "R2") (pin "1") (pinfunction "1_1") (pintype "passive"))
      (node (ref "U1") (pin "45") (pinfunction "PMODE0_45") (pintype "passive"))
    )
    (net (code "48") (name "Net-(U1-SPDLED)") (class "Default")
      (node (ref "SPD") (pin "-") (pinfunction "-_-") (pintype "passive"))
      (node (ref "U1") (pin "24") (pinfunction "SPDLED_24") (pintype "passive"))
    )
    (net (code "49") (name "Net-(U1-TOCAP)") (class "Default")
      (node (ref "C28") (pin "2") (pinfunction "2_2") (pintype "passive"))
      (node (ref "U1") (pin "20") (pinfunction "TOCAP_20") (pintype "passive"))
    )
    (net (code "50") (name "Net-(U1-XI{slash}CLKIN)") (class "Default")
      (node (ref "C25") (pin "2") (pinfunction "2_2") (pintype "passive"))
      (node (ref "U1") (pin "30") (pinfunction "XI/CLKIN_30") (pintype "passive"))
      (node (ref "X2") (pin "1") (pinfunction "1_1") (pintype "passive"))
    )
    (net (code "51") (name "Net-(U1-XO)") (class "Default")
      (node (ref "C26") (pin "2") (pinfunction "2_2") (pintype "passive"))
      (node (ref "U1") (pin "31") (pinfunction "XO_31") (pintype "passive"))
      (node (ref "X2") (pin "2") (pinfunction "2_2") (pintype "passive"))
    )
    (net (code "52") (name "Net-(U8-PA0{slash}XIN32{slash}EIC{slash}SCOM1PAD0{slash}TC2)") (class "Default")
      (node (ref "C17") (pin "1") (pinfunction "1_1") (pintype "passive"))
      (node (ref "U8") (pin "1") (pinfunction "PA0/XIN32/EIC/SCOM1PAD0/TC2_1") (pintype "bidirectional"))
      (node (ref "X1") (pin "2") (pinfunction "2_2") (pintype "passive"))
    )
    (net (code "53") (name "Net-(U8-PA1{slash}XOUT32{slash}EIC{slash}SCOM1PAD1{slash}TC2)") (class "Default")
      (node (ref "C32") (pin "1") (pinfunction "1_1") (pintype "passive"))
      (node (ref "U8") (pin "2") (pinfunction "PA1/XOUT32/EIC/SCOM1PAD1/TC2_2") (pintype "bidirectional"))
      (node (ref "X1") (pin "1") (pinfunction "1_1") (pintype "passive"))
    )
    (net (code "54") (name "Net-(U8-VDDCORE1)") (class "Default")
      (node (ref "C34") (pin "2") (pinfunction "2_2") (pintype "passive"))
      (node (ref "U8") (pin "43") (pinfunction "VDDCORE1_43") (pintype "input"))
    )
    (net (code "55") (name "Net-(USB2-A4{slash}B9{slash}VBUS)") (class "Default")
      (node (ref "F2") (pin "2") (pinfunction "2_2") (pintype "bidirectional"))
      (node (ref "USB2") (pin "A4_B9") (pinfunction "A4/B9/VBUS_A4_B9") (pintype "bidirectional"))
      (node (ref "USB2") (pin "B4_A9") (pinfunction "B4/A9/VBUS_B4_A9") (pintype "bidirectional"))
    )
    (net (code "56") (name "PA27_TX_LED") (class "Default")
      (node (ref "U8") (pin "39") (pinfunction "PA27/EIC_39") (pintype "bidirectional"))
    )
    (net (code "57") (name "PB03_RX_LED") (class "Default")
      (node (ref "U8") (pin "48") (pinfunction "PB3/EIC/AIN11/SCOM5PAD1_48") (pintype "bidirectional"))
    )
    (net (code "58") (name "POE+") (class "Default")
      (node (ref "J1") (pin "9") (pinfunction "V+_9") (pintype "bidirectional"))
      (node (ref "J15") (pin "1") (pinfunction "1_1") (pintype "bidirectional"))
    )
    (net (code "59") (name "POE-") (class "Default")
      (node (ref "J1") (pin "10") (pinfunction "V-_10") (pintype "bidirectional"))
      (node (ref "J15") (pin "2") (pinfunction "2_2") (pintype "bidirectional"))
    )
    (net (code "60") (name "RESET") (class "Default")
      (node (ref "C35") (pin "1") (pinfunction "1_1") (pintype "passive"))
      (node (ref "K1") (pin "2") (pinfunction "2_2") (pintype "bidirectional"))
      (node (ref "R4") (pin "2") (pinfunction "2_2") (pintype "passive"))
      (node (ref "U8") (pin "40") (pinfunction "RESETN_40") (pintype "bidirectional"))
    )
    (net (code "61") (name "RST_N") (class "Default")
      (node (ref "R5") (pin "1") (pinfunction "1_1") (pintype "passive"))
      (node (ref "U1") (pin "37") (pinfunction "RST_N_37") (pintype "passive"))
    )
    (net (code "62") (name "RXD2") (class "Default")
      (node (ref "J11") (pin "2") (pinfunction "2_2") (pintype "bidirectional"))
      (node (ref "U8") (pin "38") (pinfunction "PB23/EIC/SCOM5PAD3_38") (pintype "bidirectional"))
    )
    (net (code "63") (name "RXN") (class "Default")
      (node (ref "C11") (pin "1") (pinfunction "1_1") (pintype "passive"))
      (node (ref "R24") (pin "1") (pinfunction "1_1") (pintype "passive"))
      (node (ref "U1") (pin "5") (pinfunction "RXN_5") (pintype "passive"))
    )
    (net (code "64") (name "RXP") (class "Default")
      (node (ref "C12") (pin "1") (pinfunction "1_1") (pintype "passive"))
      (node (ref "R25") (pin "2") (pinfunction "2_2") (pintype "passive"))
      (node (ref "U1") (pin "6") (pinfunction "RXP_6") (pintype "passive"))
    )
    (net (code "65") (name "SCK") (class "Default")
      (node (ref "J14") (pin "3") (pinfunction "3_3") (pintype "bidirectional"))
      (node (ref "U1") (pin "33") (pinfunction "SCLK_33") (pintype "passive"))
      (node (ref "U8") (pin "20") (pinfunction "PB11/EIC/SCOM4PAD3/TC5_20") (pintype "bidirectional"))
    )
    (net (code "66") (name "SCL") (class "Default")
      (node (ref "J10") (pin "1") (pinfunction "1_1") (pintype "bidirectional"))
      (node (ref "U8") (pin "32") (pinfunction "PA23/I2C/EIC/SCOM5PAD1+/TC4_32") (pintype "bidirectional"))
    )
    (net (code "67") (name "SCS_N") (class "Default")
      (node (ref "R5") (pin "3") (pinfunction "1_3") (pintype "passive"))
      (node (ref "U1") (pin "32") (pinfunction "SCS_N_32") (pintype "passive"))
      (node (ref "U8") (pin "27") (pinfunction "PA18/EIC/SCOM1PAD2+/TC3_27") (pintype "bidirectional"))
    )
    (net (code "68") (name "SDA") (class "Default")
      (node (ref "J10") (pin "2") (pinfunction "2_2") (pintype "bidirectional"))
      (node (ref "U8") (pin "31") (pinfunction "PA22/I2C/EIC/SCOM5PAD0+/TC4_31") (pintype "bidirectional"))
    )
    (net (code "69") (name "SWCLK") (class "Default")
      (node (ref "J15") (pin "4") (pinfunction "4_4") (pintype "bidirectional"))
      (node (ref "U8") (pin "45") (pinfunction "PA30/EIC/SCOM1PAD2/TC1_45") (pintype "bidirectional"))
    )
    (net (code "70") (name "SWDIO") (class "Default")
      (node (ref "J15") (pin "5") (pinfunction "5_5") (pintype "bidirectional"))
      (node (ref "U8") (pin "46") (pinfunction "PA31/EIC/SCOM1PAD3/TC1_46") (pintype "bidirectional"))
    )
    (net (code "71") (name "TXD2") (class "Default")
      (node (ref "J11") (pin "1") (pinfunction "1_1") (pintype "bidirectional"))
      (node (ref "U8") (pin "37") (pinfunction "PB22/EIC/SCOM5PAD2_37") (pintype "bidirectional"))
    )
    (net (code "72") (name "TXN") (class "Default")
      (node (ref "J1") (pin "6") (pinfunction "6_6") (pintype "bidirectional"))
      (node (ref "R27") (pin "1") (pinfunction "1_1") (pintype "passive"))
      (node (ref "U1") (pin "1") (pinfunction "TXN_1") (pintype "passive"))
    )
    (net (code "73") (name "TXP") (class "Default")
      (node (ref "J1") (pin "5") (pinfunction "5_5") (pintype "bidirectional"))
      (node (ref "R30") (pin "1") (pinfunction "1_1") (pintype "passive"))
      (node (ref "U1") (pin "2") (pinfunction "TXP_2") (pintype "passive"))
    )
    (net (code "74") (name "USB+") (class "Default")
      (node (ref "U8") (pin "34") (pinfunction "PA25/EIC/SCOM3PAD3+/TC5_34") (pintype "bidirectional"))
      (node (ref "USB2") (pin "A6") (pinfunction "A6/DP1_A6") (pintype "bidirectional"))
      (node (ref "USB2") (pin "B6") (pinfunction "B6/DP2_B6") (pintype "bidirectional"))
    )
    (net (code "75") (name "USB-") (class "Default")
      (node (ref "U8") (pin "33") (pinfunction "PA24/EIC/SCOM3PAD2+/TC5_33") (pintype "bidirectional"))
      (node (ref "USB2") (pin "A7") (pinfunction "A7/DN1_A7") (pintype "bidirectional"))
      (node (ref "USB2") (pin "B7") (pinfunction "B7/DN2_B7") (pintype "bidirectional"))
    )
    (net (code "76") (name "WINT_N") (class "Default")
      (node (ref "R5") (pin "2") (pinfunction "1_2") (pintype "passive"))
      (node (ref "U1") (pin "36") (pinfunction "INT_N_36") (pintype "passive"))
    )
    (net (code "77") (name "unconnected-(D2-DOUT-Pad2)") (class "Default")
      (node (ref "D2") (pin "2") (pinfunction "DOUT_2") (pintype "bidirectional"))
    )
    (net (code "78") (name "unconnected-(J1-Pad7)") (class "Default")
      (node (ref "J1") (pin "7") (pinfunction "7_7") (pintype "bidirectional"))
    )
    (net (code "79") (name "unconnected-(J1-Pad8)") (class "Default")
      (node (ref "J1") (pin "8") (pinfunction "8_8") (pintype "bidirectional"))
    )
    (net (code "80") (name "unconnected-(J1-Pad15)") (class "Default")
      (node (ref "J1") (pin "15") (pinfunction "15_15") (pintype "bidirectional"))
    )
    (net (code "81") (name "unconnected-(J1-Pad16)") (class "Default")
      (node (ref "J1") (pin "16") (pinfunction "16_16") (pintype "bidirectional"))
    )
    (net (code "82") (name "unconnected-(K2-PadS1)") (class "Default")
      (node (ref "K2") (pin "S1") (pinfunction "S1_S1") (pintype "bidirectional"))
    )
    (net (code "83") (name "unconnected-(K2-PadS2)") (class "Default")
      (node (ref "K2") (pin "S2") (pinfunction "S2_S2") (pintype "bidirectional"))
    )
    (net (code "84") (name "unconnected-(U1-DNC-Pad7)") (class "Default")
      (node (ref "U1") (pin "7") (pinfunction "DNC_7") (pintype "passive"))
    )
    (net (code "85") (name "unconnected-(U1-DUPLED-Pad26)") (class "Default")
      (node (ref "U1") (pin "26") (pinfunction "DUPLED_26") (pintype "passive"))
    )
    (net (code "86") (name "unconnected-(U1-NC-Pad12)") (class "Default")
      (node (ref "U1") (pin "12") (pinfunction "NC_12") (pintype "passive"))
    )
    (net (code "87") (name "unconnected-(U1-NC-Pad13)") (class "Default")
      (node (ref "U1") (pin "13") (pinfunction "NC_13") (pintype "passive"))
    )
    (net (code "88") (name "unconnected-(U1-NC-Pad46)") (class "Default")
      (node (ref "U1") (pin "46") (pinfunction "NC_46") (pintype "passive"))
    )
    (net (code "89") (name "unconnected-(U1-NC-Pad47)") (class "Default")
      (node (ref "U1") (pin "47") (pinfunction "NC_47") (pintype "passive"))
    )
    (net (code "90") (name "unconnected-(U1-VBG-Pad18)") (class "Default")
      (node (ref "U1") (pin "18") (pinfunction "VBG_18") (pintype "passive"))
    )
    (net (code "91") (name "unconnected-(U8-PA13{slash}I2C{slash}EIC{slash}SCOM2PAD1+{slash}TC2-Pad22)") (class "Default")
      (node (ref "U8") (pin "22") (pinfunction "PA13/I2C/EIC/SCOM2PAD1+/TC2_22") (pintype "bidirectional"))
    )
    (net (code "92") (name "unconnected-(U8-PA28{slash}EIC-Pad41)") (class "Default")
      (node (ref "U8") (pin "41") (pinfunction "PA28/EIC_41") (pintype "bidirectional"))
    )
    (net (code "93") (name "unconnected-(USB2-A8{slash}SBU1-PadA8)") (class "Default")
      (node (ref "USB2") (pin "A8") (pinfunction "A8/SBU1_A8") (pintype "bidirectional"))
    )
    (net (code "94") (name "unconnected-(USB2-B8{slash}SBU2-PadB8)") (class "Default")
      (node (ref "USB2") (pin "B8") (pinfunction "B8/SBU2_B8") (pintype "bidirectional"))
    )
  )
)
